# 04_HDMII_TX.net
KiCad netlist of a schematic drawn in Altium Designer
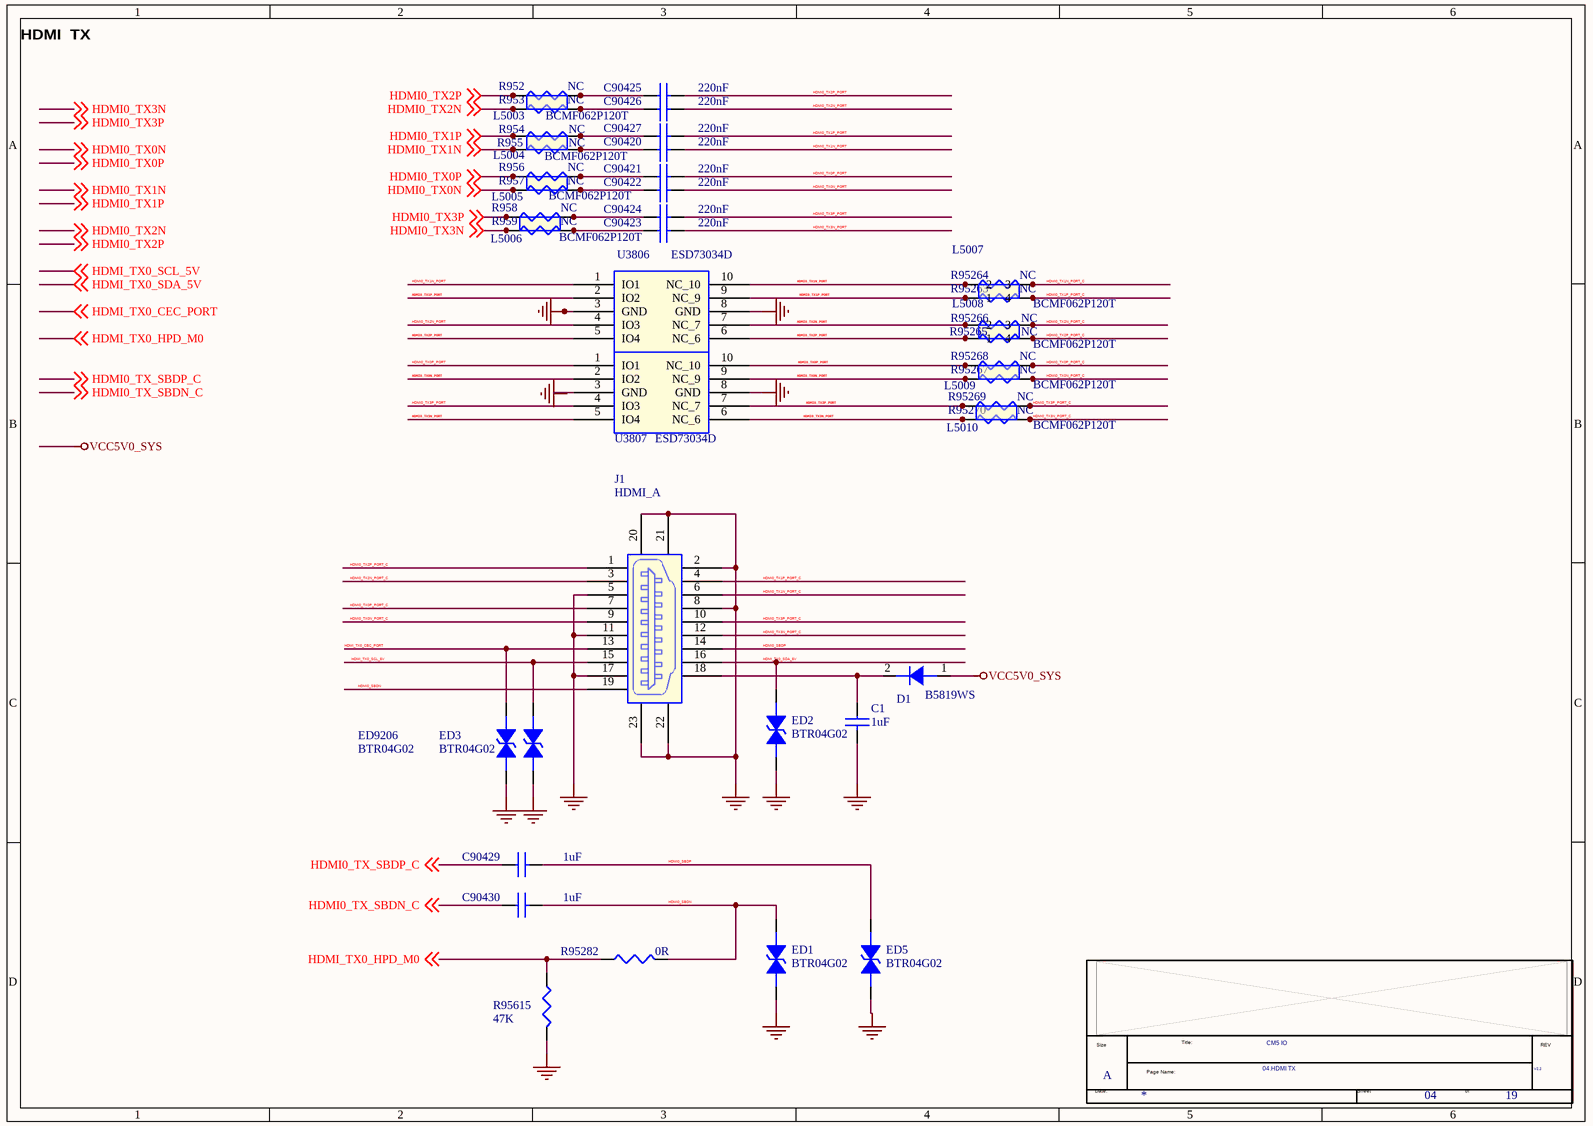
[diagram p0: 04_HDMII_TX.SchDoc]

(export (version "E")
  (design (tool "Eeschema 10.0.6"))
  (components
    (comp (ref "*")
      (value "radxa_1010")
      (fields
        (field (name "DOC") "04.HDMI TX")
        (field (name "REVCODE") "V2.2")
        (field (name "TITLE") "CM5 IO")
        (field (name "PAGE SIZE") "A")
        (field (name "PAGE NUMBER") "04")
        (field (name "PAGE COUNT") "19")
      )
      (libsource (lib "*") (part "radxa_1010"))
    )
    (comp (ref "C1")
      (value "1uF")
      (footprint "C0402")
      (description "cap,1.00uF,+/-10%,10V,X5R,C0402")
      (fields
        (field (name "VOLTAGE") "10V")
        (field (name "TOLERANCE") "10%")
        (field (name "CREATED BY") "JJJ")
      )
      (libsource (lib "*") (part "CAP NP_0"))
    )
    (comp (ref "C90420")
      (value "220nF")
      (footprint "C0201")
      (description "cap,220.00nF,+/-10%,10V,X5R,C0201")
      (fields
        (field (name "VOLTAGE") "10V")
        (field (name "TOLERANCE") "10%")
        (field (name "CREATED BY") "JJJ")
      )
      (libsource (lib "*") (part "CAP NP_0_Dup5"))
    )
    (comp (ref "C90421")
      (value "220nF")
      (footprint "C0201")
      (description "cap,220.00nF,+/-10%,10V,X5R,C0201")
      (fields
        (field (name "VOLTAGE") "10V")
        (field (name "TOLERANCE") "10%")
        (field (name "CREATED BY") "JJJ")
      )
      (libsource (lib "*") (part "CAP NP_0_Dup5"))
    )
    (comp (ref "C90422")
      (value "220nF")
      (footprint "C0201")
      (description "cap,220.00nF,+/-10%,10V,X5R,C0201")
      (fields
        (field (name "VOLTAGE") "10V")
        (field (name "TOLERANCE") "10%")
        (field (name "CREATED BY") "JJJ")
      )
      (libsource (lib "*") (part "CAP NP_0_Dup5"))
    )
    (comp (ref "C90423")
      (value "220nF")
      (footprint "C0201")
      (description "cap,220.00nF,+/-10%,10V,X5R,C0201")
      (fields
        (field (name "VOLTAGE") "10V")
        (field (name "TOLERANCE") "10%")
        (field (name "CREATED BY") "JJJ")
      )
      (libsource (lib "*") (part "CAP NP_0_Dup5"))
    )
    (comp (ref "C90424")
      (value "220nF")
      (footprint "C0201")
      (description "cap,220.00nF,+/-10%,10V,X5R,C0201")
      (fields
        (field (name "VOLTAGE") "10V")
        (field (name "TOLERANCE") "10%")
        (field (name "CREATED BY") "JJJ")
      )
      (libsource (lib "*") (part "CAP NP_0_Dup5"))
    )
    (comp (ref "C90425")
      (value "220nF")
      (footprint "C0201")
      (description "cap,220.00nF,+/-10%,10V,X5R,C0201")
      (fields
        (field (name "VOLTAGE") "10V")
        (field (name "MANUFACTURER") "TDK")
        (field (name "CREATED BY") "JJJ")
      )
      (libsource (lib "*") (part "CAP NP_0_Dup5"))
    )
    (comp (ref "C90426")
      (value "220nF")
      (footprint "C0201")
      (description "cap,220.00nF,+/-10%,10V,X5R,C0201")
      (fields
        (field (name "VOLTAGE") "10V")
        (field (name "MANUFACTURER") "TDK")
        (field (name "CREATED BY") "JJJ")
      )
      (libsource (lib "*") (part "CAP NP_0_Dup5"))
    )
    (comp (ref "C90427")
      (value "220nF")
      (footprint "C0201")
      (description "cap,220.00nF,+/-10%,10V,X5R,C0201")
      (fields
        (field (name "VOLTAGE") "10V")
        (field (name "TOLERANCE") "10%")
        (field (name "CREATED BY") "JJJ")
      )
      (libsource (lib "*") (part "CAP NP_0_Dup5"))
    )
    (comp (ref "C90429")
      (value "1uF")
      (footprint "C0201")
      (description "cap,1.00uF,+/-10%,10V,X5R,C0402")
      (fields
        (field (name "VOLTAGE") "10V")
        (field (name "MANUFACTURER") "TDK")
        (field (name "CREATED BY") "JJJ")
      )
      (libsource (lib "*") (part "CAP NP_0_Dup5"))
    )
    (comp (ref "C90430")
      (value "1uF")
      (footprint "C0201")
      (description "cap,1.00uF,+/-10%,10V,X5R,C0402")
      (fields
        (field (name "VOLTAGE") "10V")
        (field (name "MANUFACTURER") "TDK")
        (field (name "CREATED BY") "JJJ")
      )
      (libsource (lib "*") (part "CAP NP_0_Dup5"))
    )
    (comp (ref "D1")
      (value "B5819WS")
      (footprint "SOD_323")
      (description "Schottky Barrier，B5819WS SOD-323")
      (fields (field (name "MANUFACTURER") "长电") (field (name "CREATED BY") "JJJ"))
      (libsource (lib "*") (part "DIODE_Dup1"))
    )
    (comp (ref "ED1")
      (value "BTR04G02")
      (footprint "ESD0402_1xD5")
      (description "1-Line, Bi-directional, Transient Voltage Suppressors.17.5pF.")
      (fields (field (name "MANUFACTURER") "WillSemi(韦尔半导体)") (field (name "CREATED BY") "JJJ"))
      (libsource (lib "*") (part "DIODE BI_DIR TRIG_2"))
    )
    (comp (ref "ED2")
      (value "BTR04G02")
      (footprint "ESD0402_1xD5")
      (description "1-Line, Bi-directional, Transient Voltage Suppressors.17.5pF.")
      (fields (field (name "MANUFACTURER") "WillSemi(韦尔半导体)") (field (name "CREATED BY") "JJJ"))
      (libsource (lib "*") (part "DIODE BI_DIR TRIG_2"))
    )
    (comp (ref "ED3")
      (value "BTR04G02")
      (footprint "ESD0402_1xD5")
      (description "1-Line, Bi-directional, Transient Voltage Suppressors.17.5pF.")
      (fields (field (name "MANUFACTURER") "WillSemi(韦尔半导体)") (field (name "CREATED BY") "JJJ"))
      (libsource (lib "*") (part "DIODE BI_DIR TRIG_2"))
    )
    (comp (ref "ED5")
      (value "BTR04G02")
      (footprint "ESD0402_1xD5")
      (description "1-Line, Bi-directional, Transient Voltage Suppressors.17.5pF.")
      (fields (field (name "MANUFACTURER") "WillSemi(韦尔半导体)") (field (name "CREATED BY") "JJJ"))
      (libsource (lib "*") (part "DIODE BI_DIR TRIG_2"))
    )
    (comp (ref "ED9206")
      (value "BTR04G02")
      (footprint "ESD0402_1xD5")
      (description "1-Line, Bi-directional, Transient Voltage Suppressors.17.5pF.")
      (fields (field (name "MANUFACTURER") "WillSemi(韦尔半导体)") (field (name "CREATED BY") "JJJ"))
      (libsource (lib "*") (part "DIODE BI_DIR TRIG_2"))
    )
    (comp (ref "J1")
      (value "HDMI_A")
      (footprint "HDMIA19S")
      (description "通用A型HDMI座,卧式,侧插")
      (fields (field (name "MANUFACTURER") "旺科达") (field (name "CREATED BY") "JJJ"))
      (libsource (lib "*") (part "HDMI_A"))
    )
    (comp (ref "L5003")
      (value "BCMF062P120T")
      (footprint "MCZ1210AH900L2")
      (libsource (lib "*") (part "MCZ1210AH900L2_2"))
    )
    (comp (ref "L5004")
      (value "BCMF062P120T")
      (footprint "MCZ1210AH900L2")
      (libsource (lib "*") (part "MCZ1210AH900L2_2"))
    )
    (comp (ref "L5005")
      (value "BCMF062P120T")
      (footprint "MCZ1210AH900L2")
      (libsource (lib "*") (part "MCZ1210AH900L2_2"))
    )
    (comp (ref "L5006")
      (value "BCMF062P120T")
      (footprint "MCZ1210AH900L2")
      (libsource (lib "*") (part "MCZ1210AH900L2_2"))
    )
    (comp (ref "L5007")
      (value "BCMF062P120T")
      (footprint "MCZ1210AH900L2")
      (libsource (lib "*") (part "MCZ1210AH900L2_0"))
    )
    (comp (ref "L5008")
      (value "BCMF062P120T")
      (footprint "MCZ1210AH900L2")
      (libsource (lib "*") (part "MCZ1210AH900L2_1"))
    )
    (comp (ref "L5009")
      (value "BCMF062P120T")
      (footprint "MCZ1210AH900L2")
      (libsource (lib "*") (part "MCZ1210AH900L2_2"))
    )
    (comp (ref "L5010")
      (value "BCMF062P120T")
      (footprint "MCZ1210AH900L2")
      (libsource (lib "*") (part "MCZ1210AH900L2_2"))
    )
    (comp (ref "R952")
      (value "NC")
      (footprint "R0402")
      (description "通用厚膜电阻,1K2,+/-5%,R0402,1/16W.")
      (fields
        (field (name "TOLERANCE") "5%")
        (field (name "MANUFACTURER") "YAGEO")
        (field (name "CREATED BY") "YTL")
      )
      (libsource (lib "*") (part "RESISTOR_1_Dup1"))
    )
    (comp (ref "R953")
      (value "NC")
      (footprint "R0402")
      (description "通用厚膜电阻,1K2,+/-5%,R0402,1/16W.")
      (fields
        (field (name "TOLERANCE") "5%")
        (field (name "MANUFACTURER") "YAGEO")
        (field (name "CREATED BY") "YTL")
      )
      (libsource (lib "*") (part "RESISTOR_1_Dup1"))
    )
    (comp (ref "R954")
      (value "NC")
      (footprint "R0402")
      (description "通用厚膜电阻,1K2,+/-5%,R0402,1/16W.")
      (fields
        (field (name "TOLERANCE") "5%")
        (field (name "MANUFACTURER") "YAGEO")
        (field (name "CREATED BY") "YTL")
      )
      (libsource (lib "*") (part "RESISTOR_1_Dup1"))
    )
    (comp (ref "R955")
      (value "NC")
      (footprint "R0402")
      (description "通用厚膜电阻,1K2,+/-5%,R0402,1/16W.")
      (fields
        (field (name "TOLERANCE") "5%")
        (field (name "MANUFACTURER") "YAGEO")
        (field (name "CREATED BY") "YTL")
      )
      (libsource (lib "*") (part "RESISTOR_1_Dup1"))
    )
    (comp (ref "R956")
      (value "NC")
      (footprint "R0402")
      (description "通用厚膜电阻,1K2,+/-5%,R0402,1/16W.")
      (fields
        (field (name "TOLERANCE") "5%")
        (field (name "MANUFACTURER") "YAGEO")
        (field (name "CREATED BY") "YTL")
      )
      (libsource (lib "*") (part "RESISTOR_1_Dup1"))
    )
    (comp (ref "R957")
      (value "NC")
      (footprint "R0402")
      (description "通用厚膜电阻,1K2,+/-5%,R0402,1/16W.")
      (fields
        (field (name "TOLERANCE") "5%")
        (field (name "MANUFACTURER") "YAGEO")
        (field (name "CREATED BY") "YTL")
      )
      (libsource (lib "*") (part "RESISTOR_1_Dup1"))
    )
    (comp (ref "R958")
      (value "NC")
      (footprint "R0402")
      (description "通用厚膜电阻,1K2,+/-5%,R0402,1/16W.")
      (fields
        (field (name "TOLERANCE") "5%")
        (field (name "MANUFACTURER") "YAGEO")
        (field (name "CREATED BY") "YTL")
      )
      (libsource (lib "*") (part "RESISTOR_1_Dup1"))
    )
    (comp (ref "R959")
      (value "NC")
      (footprint "R0402")
      (description "通用厚膜电阻,1K2,+/-5%,R0402,1/16W.")
      (fields
        (field (name "TOLERANCE") "5%")
        (field (name "MANUFACTURER") "YAGEO")
        (field (name "CREATED BY") "YTL")
      )
      (libsource (lib "*") (part "RESISTOR_1_Dup1"))
    )
    (comp (ref "R95263")
      (value "NC")
      (footprint "R0402")
      (description "通用厚膜电阻,1K2,+/-5%,R0402,1/16W.")
      (fields
        (field (name "TOLERANCE") "5%")
        (field (name "MANUFACTURER") "YAGEO")
        (field (name "CREATED BY") "YTL")
      )
      (libsource (lib "*") (part "RESISTOR_1_Dup1"))
    )
    (comp (ref "R95264")
      (value "NC")
      (footprint "R0402")
      (description "通用厚膜电阻,1K2,+/-5%,R0402,1/16W.")
      (fields
        (field (name "TOLERANCE") "5%")
        (field (name "MANUFACTURER") "YAGEO")
        (field (name "CREATED BY") "YTL")
      )
      (libsource (lib "*") (part "RESISTOR_1_Dup1"))
    )
    (comp (ref "R95265")
      (value "NC")
      (footprint "R0402")
      (description "通用厚膜电阻,1K2,+/-5%,R0402,1/16W.")
      (fields
        (field (name "TOLERANCE") "5%")
        (field (name "MANUFACTURER") "YAGEO")
        (field (name "CREATED BY") "YTL")
      )
      (libsource (lib "*") (part "RESISTOR_1_Dup1"))
    )
    (comp (ref "R95266")
      (value "NC")
      (footprint "R0402")
      (description "通用厚膜电阻,1K2,+/-5%,R0402,1/16W.")
      (fields
        (field (name "TOLERANCE") "5%")
        (field (name "MANUFACTURER") "YAGEO")
        (field (name "CREATED BY") "YTL")
      )
      (libsource (lib "*") (part "RESISTOR_1_Dup1"))
    )
    (comp (ref "R95267")
      (value "NC")
      (footprint "R0402")
      (description "通用厚膜电阻,1K2,+/-5%,R0402,1/16W.")
      (fields
        (field (name "TOLERANCE") "5%")
        (field (name "MANUFACTURER") "YAGEO")
        (field (name "CREATED BY") "YTL")
      )
      (libsource (lib "*") (part "RESISTOR_1_Dup1"))
    )
    (comp (ref "R95268")
      (value "NC")
      (footprint "R0402")
      (description "通用厚膜电阻,1K2,+/-5%,R0402,1/16W.")
      (fields
        (field (name "TOLERANCE") "5%")
        (field (name "MANUFACTURER") "YAGEO")
        (field (name "CREATED BY") "YTL")
      )
      (libsource (lib "*") (part "RESISTOR_1_Dup1"))
    )
    (comp (ref "R95269")
      (value "NC")
      (footprint "R0402")
      (description "通用厚膜电阻,1K2,+/-5%,R0402,1/16W.")
      (fields
        (field (name "TOLERANCE") "5%")
        (field (name "MANUFACTURER") "YAGEO")
        (field (name "CREATED BY") "YTL")
      )
      (libsource (lib "*") (part "RESISTOR_1_Dup1"))
    )
    (comp (ref "R95270")
      (value "NC")
      (footprint "R0402")
      (description "通用厚膜电阻,1K2,+/-5%,R0402,1/16W.")
      (fields
        (field (name "TOLERANCE") "5%")
        (field (name "MANUFACTURER") "YAGEO")
        (field (name "CREATED BY") "YTL")
      )
      (libsource (lib "*") (part "RESISTOR_1_Dup1"))
    )
    (comp (ref "R95282")
      (value "0R")
      (footprint "R0402")
      (description "通用厚膜电阻,1K2,+/-5%,R0402,1/16W.")
      (fields
        (field (name "TOLERANCE") "5%")
        (field (name "MANUFACTURER") "YAGEO")
        (field (name "CREATED BY") "YTL")
      )
      (libsource (lib "*") (part "RESISTOR_0_Dup2"))
    )
    (comp (ref "R95615")
      (value "47K")
      (footprint "R0402")
      (description "通用厚膜电阻,2K49,+/-1%,R0402,1/16W.")
      (fields
        (field (name "TOLERANCE") "1%")
        (field (name "MANUFACTURER") "YAGEO")
        (field (name "CREATED BY") "YTL")
      )
      (libsource (lib "*") (part "RESISTOR_0_Dup4"))
    )
    (comp (ref "U3806")
      (value "ESD73034D")
      (footprint "SON10_2R50X1R00X0R50")
      (description "4-Lines, Bi-directional, Ultra-low Capacitance Transient Voltage Suppressors")
      (fields (field (name "MANUFACTURER") "WillSemi(韦尔半导体)") (field (name "CREATED BY") "YWQ"))
      (libsource (lib "*") (part "ESD_ESD73034D"))
    )
    (comp (ref "U3807")
      (value "ESD73034D")
      (footprint "SON10_2R50X1R00X0R50")
      (description "4-Lines, Bi-directional, Ultra-low Capacitance Transient Voltage Suppressors")
      (fields (field (name "MANUFACTURER") "WillSemi(韦尔半导体)") (field (name "CREATED BY") "YWQ"))
      (libsource (lib "*") (part "ESD_ESD73034D"))
    )
  )
  (nets
    (net (code "1") (name "/HDMI0_SBDN") (class "Default")
      (node (ref "C90430") (pin "2") (pinfunction "2_2") (pintype "passive"))
      (node (ref "ED1") (pin "1") (pinfunction "1_1") (pintype "passive"))
      (node (ref "J1") (pin "19") (pinfunction "19_19") (pintype "passive"))
      (node (ref "R95282") (pin "2") (pinfunction "2_2") (pintype "passive"))
    )
    (net (code "2") (name "/HDMI0_SBDP") (class "Default")
      (node (ref "C90429") (pin "2") (pinfunction "2_2") (pintype "passive"))
      (node (ref "ED5") (pin "1") (pinfunction "1_1") (pintype "passive"))
      (node (ref "J1") (pin "14") (pinfunction "14_14") (pintype "passive"))
    )
    (net (code "3") (name "/HDMI0_TX0N_PORT") (class "Default")
      (node (ref "C90422") (pin "2") (pinfunction "2_2") (pintype "passive"))
      (node (ref "L5009") (pin "2") (pinfunction "2_2") (pintype "passive"))
      (node (ref "R95267") (pin "1") (pinfunction "1_1") (pintype "passive"))
      (node (ref "U3807") (pin "2") (pinfunction "IO2_2") (pintype "passive"))
      (node (ref "U3807") (pin "9") (pinfunction "NC_9_9") (pintype "passive"))
    )
    (net (code "4") (name "/HDMI0_TX0N_PORT_C") (class "Default")
      (node (ref "J1") (pin "9") (pinfunction "9_9") (pintype "passive"))
      (node (ref "L5009") (pin "3") (pinfunction "3_3") (pintype "passive"))
      (node (ref "R95267") (pin "2") (pinfunction "2_2") (pintype "passive"))
    )
    (net (code "5") (name "/HDMI0_TX0P_PORT") (class "Default")
      (node (ref "C90421") (pin "2") (pinfunction "2_2") (pintype "passive"))
      (node (ref "L5009") (pin "1") (pinfunction "1_1") (pintype "passive"))
      (node (ref "R95268") (pin "1") (pinfunction "1_1") (pintype "passive"))
      (node (ref "U3807") (pin "1") (pinfunction "IO1_1") (pintype "passive"))
      (node (ref "U3807") (pin "10") (pinfunction "NC_10_10") (pintype "passive"))
    )
    (net (code "6") (name "/HDMI0_TX0P_PORT_C") (class "Default")
      (node (ref "J1") (pin "7") (pinfunction "7_7") (pintype "passive"))
      (node (ref "L5009") (pin "4") (pinfunction "4_4") (pintype "passive"))
      (node (ref "R95268") (pin "2") (pinfunction "2_2") (pintype "passive"))
    )
    (net (code "7") (name "/HDMI0_TX1N_PORT") (class "Default")
      (node (ref "C90420") (pin "2") (pinfunction "2_2") (pintype "passive"))
      (node (ref "L5007") (pin "2") (pinfunction "2_2") (pintype "passive"))
      (node (ref "R95264") (pin "1") (pinfunction "1_1") (pintype "passive"))
      (node (ref "U3806") (pin "1") (pinfunction "IO1_1") (pintype "passive"))
      (node (ref "U3806") (pin "10") (pinfunction "NC_10_10") (pintype "passive"))
    )
    (net (code "8") (name "/HDMI0_TX1N_PORT_C") (class "Default")
      (node (ref "J1") (pin "6") (pinfunction "6_6") (pintype "passive"))
      (node (ref "L5007") (pin "3") (pinfunction "3_3") (pintype "passive"))
      (node (ref "R95264") (pin "2") (pinfunction "2_2") (pintype "passive"))
    )
    (net (code "9") (name "/HDMI0_TX1P_PORT") (class "Default")
      (node (ref "C90427") (pin "2") (pinfunction "2_2") (pintype "passive"))
      (node (ref "L5007") (pin "1") (pinfunction "1_1") (pintype "passive"))
      (node (ref "R95263") (pin "1") (pinfunction "1_1") (pintype "passive"))
      (node (ref "U3806") (pin "2") (pinfunction "IO2_2") (pintype "passive"))
      (node (ref "U3806") (pin "9") (pinfunction "NC_9_9") (pintype "passive"))
    )
    (net (code "10") (name "/HDMI0_TX1P_PORT_C") (class "Default")
      (node (ref "J1") (pin "4") (pinfunction "4_4") (pintype "passive"))
      (node (ref "L5007") (pin "4") (pinfunction "4_4") (pintype "passive"))
      (node (ref "R95263") (pin "2") (pinfunction "2_2") (pintype "passive"))
    )
    (net (code "11") (name "/HDMI0_TX2N_PORT") (class "Default")
      (node (ref "C90426") (pin "2") (pinfunction "2_2") (pintype "passive"))
      (node (ref "L5008") (pin "2") (pinfunction "2_2") (pintype "passive"))
      (node (ref "R95266") (pin "1") (pinfunction "1_1") (pintype "passive"))
      (node (ref "U3806") (pin "4") (pinfunction "IO3_4") (pintype "passive"))
      (node (ref "U3806") (pin "7") (pinfunction "NC_7_7") (pintype "passive"))
    )
    (net (code "12") (name "/HDMI0_TX2N_PORT_C") (class "Default")
      (node (ref "J1") (pin "3") (pinfunction "3_3") (pintype "passive"))
      (node (ref "L5008") (pin "3") (pinfunction "3_3") (pintype "passive"))
      (node (ref "R95266") (pin "2") (pinfunction "2_2") (pintype "passive"))
    )
    (net (code "13") (name "/HDMI0_TX2P_PORT") (class "Default")
      (node (ref "C90425") (pin "2") (pinfunction "2_2") (pintype "passive"))
      (node (ref "L5008") (pin "1") (pinfunction "1_1") (pintype "passive"))
      (node (ref "R95265") (pin "1") (pinfunction "1_1") (pintype "passive"))
      (node (ref "U3806") (pin "5") (pinfunction "IO4_5") (pintype "passive"))
      (node (ref "U3806") (pin "6") (pinfunction "NC_6_6") (pintype "passive"))
    )
    (net (code "14") (name "/HDMI0_TX2P_PORT_C") (class "Default")
      (node (ref "J1") (pin "1") (pinfunction "$PIN0_1") (pintype "passive"))
      (node (ref "L5008") (pin "4") (pinfunction "4_4") (pintype "passive"))
      (node (ref "R95265") (pin "2") (pinfunction "2_2") (pintype "passive"))
    )
    (net (code "15") (name "/HDMI0_TX3N_PORT") (class "Default")
      (node (ref "C90423") (pin "2") (pinfunction "2_2") (pintype "passive"))
      (node (ref "L5010") (pin "2") (pinfunction "2_2") (pintype "passive"))
      (node (ref "R95270") (pin "1") (pinfunction "1_1") (pintype "passive"))
      (node (ref "U3807") (pin "5") (pinfunction "IO4_5") (pintype "passive"))
      (node (ref "U3807") (pin "6") (pinfunction "NC_6_6") (pintype "passive"))
    )
    (net (code "16") (name "/HDMI0_TX3N_PORT_C") (class "Default")
      (node (ref "J1") (pin "12") (pinfunction "12_12") (pintype "passive"))
      (node (ref "L5010") (pin "3") (pinfunction "3_3") (pintype "passive"))
      (node (ref "R95270") (pin "2") (pinfunction "2_2") (pintype "passive"))
    )
    (net (code "17") (name "/HDMI0_TX3P_PORT") (class "Default")
      (node (ref "C90424") (pin "2") (pinfunction "2_2") (pintype "passive"))
      (node (ref "L5010") (pin "1") (pinfunction "1_1") (pintype "passive"))
      (node (ref "R95269") (pin "1") (pinfunction "1_1") (pintype "passive"))
      (node (ref "U3807") (pin "4") (pinfunction "IO3_4") (pintype "passive"))
      (node (ref "U3807") (pin "7") (pinfunction "NC_7_7") (pintype "passive"))
    )
    (net (code "18") (name "/HDMI0_TX3P_PORT_C") (class "Default")
      (node (ref "J1") (pin "10") (pinfunction "10_10") (pintype "passive"))
      (node (ref "L5010") (pin "4") (pinfunction "4_4") (pintype "passive"))
      (node (ref "R95269") (pin "2") (pinfunction "2_2") (pintype "passive"))
    )
    (net (code "19") (name "GND") (class "Default")
      (node (ref "C1") (pin "2") (pinfunction "2_2") (pintype "passive"))
      (node (ref "ED1") (pin "2") (pinfunction "2_2") (pintype "passive"))
      (node (ref "ED2") (pin "2") (pinfunction "2_2") (pintype "passive"))
      (node (ref "ED3") (pin "2") (pinfunction "2_2") (pintype "passive"))
      (node (ref "ED5") (pin "2") (pinfunction "2_2") (pintype "passive"))
      (node (ref "ED9206") (pin "2") (pinfunction "2_2") (pintype "passive"))
      (node (ref "J1") (pin "11") (pinfunction "11_11") (pintype "passive"))
      (node (ref "J1") (pin "17") (pinfunction "17_17") (pintype "passive"))
      (node (ref "J1") (pin "2") (pinfunction "2_2") (pintype "passive"))
      (node (ref "J1") (pin "20") (pinfunction "20_20") (pintype "passive"))
      (node (ref "J1") (pin "21") (pinfunction "21_21") (pintype "passive"))
      (node (ref "J1") (pin "22") (pinfunction "22_22") (pintype "passive"))
      (node (ref "J1") (pin "23") (pinfunction "23_23") (pintype "passive"))
      (node (ref "J1") (pin "5") (pinfunction "5_5") (pintype "passive"))
      (node (ref "J1") (pin "8") (pinfunction "8_8") (pintype "passive"))
      (node (ref "R95615") (pin "2") (pinfunction "2_2") (pintype "passive"))
      (node (ref "U3806") (pin "3") (pinfunction "GND_3") (pintype "power_in"))
      (node (ref "U3806") (pin "8") (pinfunction "GND_8") (pintype "power_in"))
      (node (ref "U3807") (pin "8") (pinfunction "GND_8") (pintype "power_in"))
    )
    (net (code "20") (name "HDMI0_TX0N") (class "Default")
      (node (ref "L5005") (pin "2") (pinfunction "2_2") (pintype "passive"))
      (node (ref "R957") (pin "1") (pinfunction "1_1") (pintype "passive"))
    )
    (net (code "21") (name "HDMI0_TX0P") (class "Default")
      (node (ref "L5005") (pin "1") (pinfunction "1_1") (pintype "passive"))
      (node (ref "R956") (pin "1") (pinfunction "1_1") (pintype "passive"))
    )
    (net (code "22") (name "HDMI0_TX1N") (class "Default")
      (node (ref "L5004") (pin "2") (pinfunction "2_2") (pintype "passive"))
      (node (ref "R955") (pin "1") (pinfunction "1_1") (pintype "passive"))
    )
    (net (code "23") (name "HDMI0_TX1P") (class "Default")
      (node (ref "L5004") (pin "1") (pinfunction "1_1") (pintype "passive"))
      (node (ref "R954") (pin "1") (pinfunction "1_1") (pintype "passive"))
    )
    (net (code "24") (name "HDMI0_TX2N") (class "Default")
      (node (ref "L5003") (pin "2") (pinfunction "2_2") (pintype "passive"))
      (node (ref "R953") (pin "1") (pinfunction "1_1") (pintype "passive"))
    )
    (net (code "25") (name "HDMI0_TX2P") (class "Default")
      (node (ref "L5003") (pin "1") (pinfunction "1_1") (pintype "passive"))
      (node (ref "R952") (pin "1") (pinfunction "1_1") (pintype "passive"))
    )
    (net (code "26") (name "HDMI0_TX3N") (class "Default")
      (node (ref "L5006") (pin "2") (pinfunction "2_2") (pintype "passive"))
      (node (ref "R959") (pin "1") (pinfunction "1_1") (pintype "passive"))
    )
    (net (code "27") (name "HDMI0_TX3P") (class "Default")
      (node (ref "L5006") (pin "1") (pinfunction "1_1") (pintype "passive"))
      (node (ref "R958") (pin "1") (pinfunction "1_1") (pintype "passive"))
    )
    (net (code "28") (name "HDMI0_TX_SBDN_C") (class "Default")
      (node (ref "C90430") (pin "1") (pinfunction "1_1") (pintype "passive"))
    )
    (net (code "29") (name "HDMI0_TX_SBDP_C") (class "Default")
      (node (ref "C90429") (pin "1") (pinfunction "1_1") (pintype "passive"))
    )
    (net (code "30") (name "HDMI_TX0_CEC_PORT") (class "Default")
      (node (ref "ED9206") (pin "1") (pinfunction "1_1") (pintype "passive"))
      (node (ref "J1") (pin "13") (pinfunction "13_13") (pintype "passive"))
    )
    (net (code "31") (name "HDMI_TX0_HPD_M0") (class "Default")
      (node (ref "R95282") (pin "1") (pinfunction "1_1") (pintype "passive"))
      (node (ref "R95615") (pin "1") (pinfunction "1_1") (pintype "passive"))
    )
    (net (code "32") (name "HDMI_TX0_SCL_5V") (class "Default")
      (node (ref "ED3") (pin "1") (pinfunction "1_1") (pintype "passive"))
      (node (ref "J1") (pin "15") (pinfunction "15_15") (pintype "passive"))
    )
    (net (code "33") (name "HDMI_TX0_SDA_5V") (class "Default")
      (node (ref "ED2") (pin "1") (pinfunction "1_1") (pintype "passive"))
      (node (ref "J1") (pin "16") (pinfunction "16_16") (pintype "passive"))
    )
    (net (code "34") (name "Net-(C90420-Pad1)") (class "Default")
      (node (ref "C90420") (pin "1") (pinfunction "1_1") (pintype "passive"))
      (node (ref "L5004") (pin "3") (pinfunction "3_3") (pintype "passive"))
      (node (ref "R955") (pin "2") (pinfunction "2_2") (pintype "passive"))
    )
    (net (code "35") (name "Net-(C90421-Pad1)") (class "Default")
      (node (ref "C90421") (pin "1") (pinfunction "1_1") (pintype "passive"))
      (node (ref "L5005") (pin "4") (pinfunction "4_4") (pintype "passive"))
      (node (ref "R956") (pin "2") (pinfunction "2_2") (pintype "passive"))
    )
    (net (code "36") (name "Net-(C90422-Pad1)") (class "Default")
      (node (ref "C90422") (pin "1") (pinfunction "1_1") (pintype "passive"))
      (node (ref "L5005") (pin "3") (pinfunction "3_3") (pintype "passive"))
      (node (ref "R957") (pin "2") (pinfunction "2_2") (pintype "passive"))
    )
    (net (code "37") (name "Net-(C90423-Pad1)") (class "Default")
      (node (ref "C90423") (pin "1") (pinfunction "1_1") (pintype "passive"))
      (node (ref "L5006") (pin "3") (pinfunction "3_3") (pintype "passive"))
      (node (ref "R959") (pin "2") (pinfunction "2_2") (pintype "passive"))
    )
    (net (code "38") (name "Net-(C90424-Pad1)") (class "Default")
      (node (ref "C90424") (pin "1") (pinfunction "1_1") (pintype "passive"))
      (node (ref "L5006") (pin "4") (pinfunction "4_4") (pintype "passive"))
      (node (ref "R958") (pin "2") (pinfunction "2_2") (pintype "passive"))
    )
    (net (code "39") (name "Net-(C90425-Pad1)") (class "Default")
      (node (ref "C90425") (pin "1") (pinfunction "1_1") (pintype "passive"))
      (node (ref "L5003") (pin "4") (pinfunction "4_4") (pintype "passive"))
      (node (ref "R952") (pin "2") (pinfunction "2_2") (pintype "passive"))
    )
    (net (code "40") (name "Net-(C90426-Pad1)") (class "Default")
      (node (ref "C90426") (pin "1") (pinfunction "1_1") (pintype "passive"))
      (node (ref "L5003") (pin "3") (pinfunction "3_3") (pintype "passive"))
      (node (ref "R953") (pin "2") (pinfunction "2_2") (pintype "passive"))
    )
    (net (code "41") (name "Net-(C90427-Pad1)") (class "Default")
      (node (ref "C90427") (pin "1") (pinfunction "1_1") (pintype "passive"))
      (node (ref "L5004") (pin "4") (pinfunction "4_4") (pintype "passive"))
      (node (ref "R954") (pin "2") (pinfunction "2_2") (pintype "passive"))
    )
    (net (code "42") (name "Net-(D1-K)") (class "Default")
      (node (ref "C1") (pin "1") (pinfunction "1_1") (pintype "passive"))
      (node (ref "D1") (pin "2") (pinfunction "K_2") (pintype "passive"))
      (node (ref "J1") (pin "18") (pinfunction "18_18") (pintype "passive"))
    )
    (net (code "43") (name "VCC5V0_SYS") (class "Default")
      (node (ref "D1") (pin "1") (pinfunction "A_1") (pintype "passive"))
    )
    (net (code "44") (name "unconnected-(U3807-GND-Pad3)") (class "Default")
      (node (ref "U3807") (pin "3") (pinfunction "GND_3") (pintype "power_in"))
    )
  )
)
